# pw_dist_v2.net
KiCad netlist of a schematic drawn in EAGLE
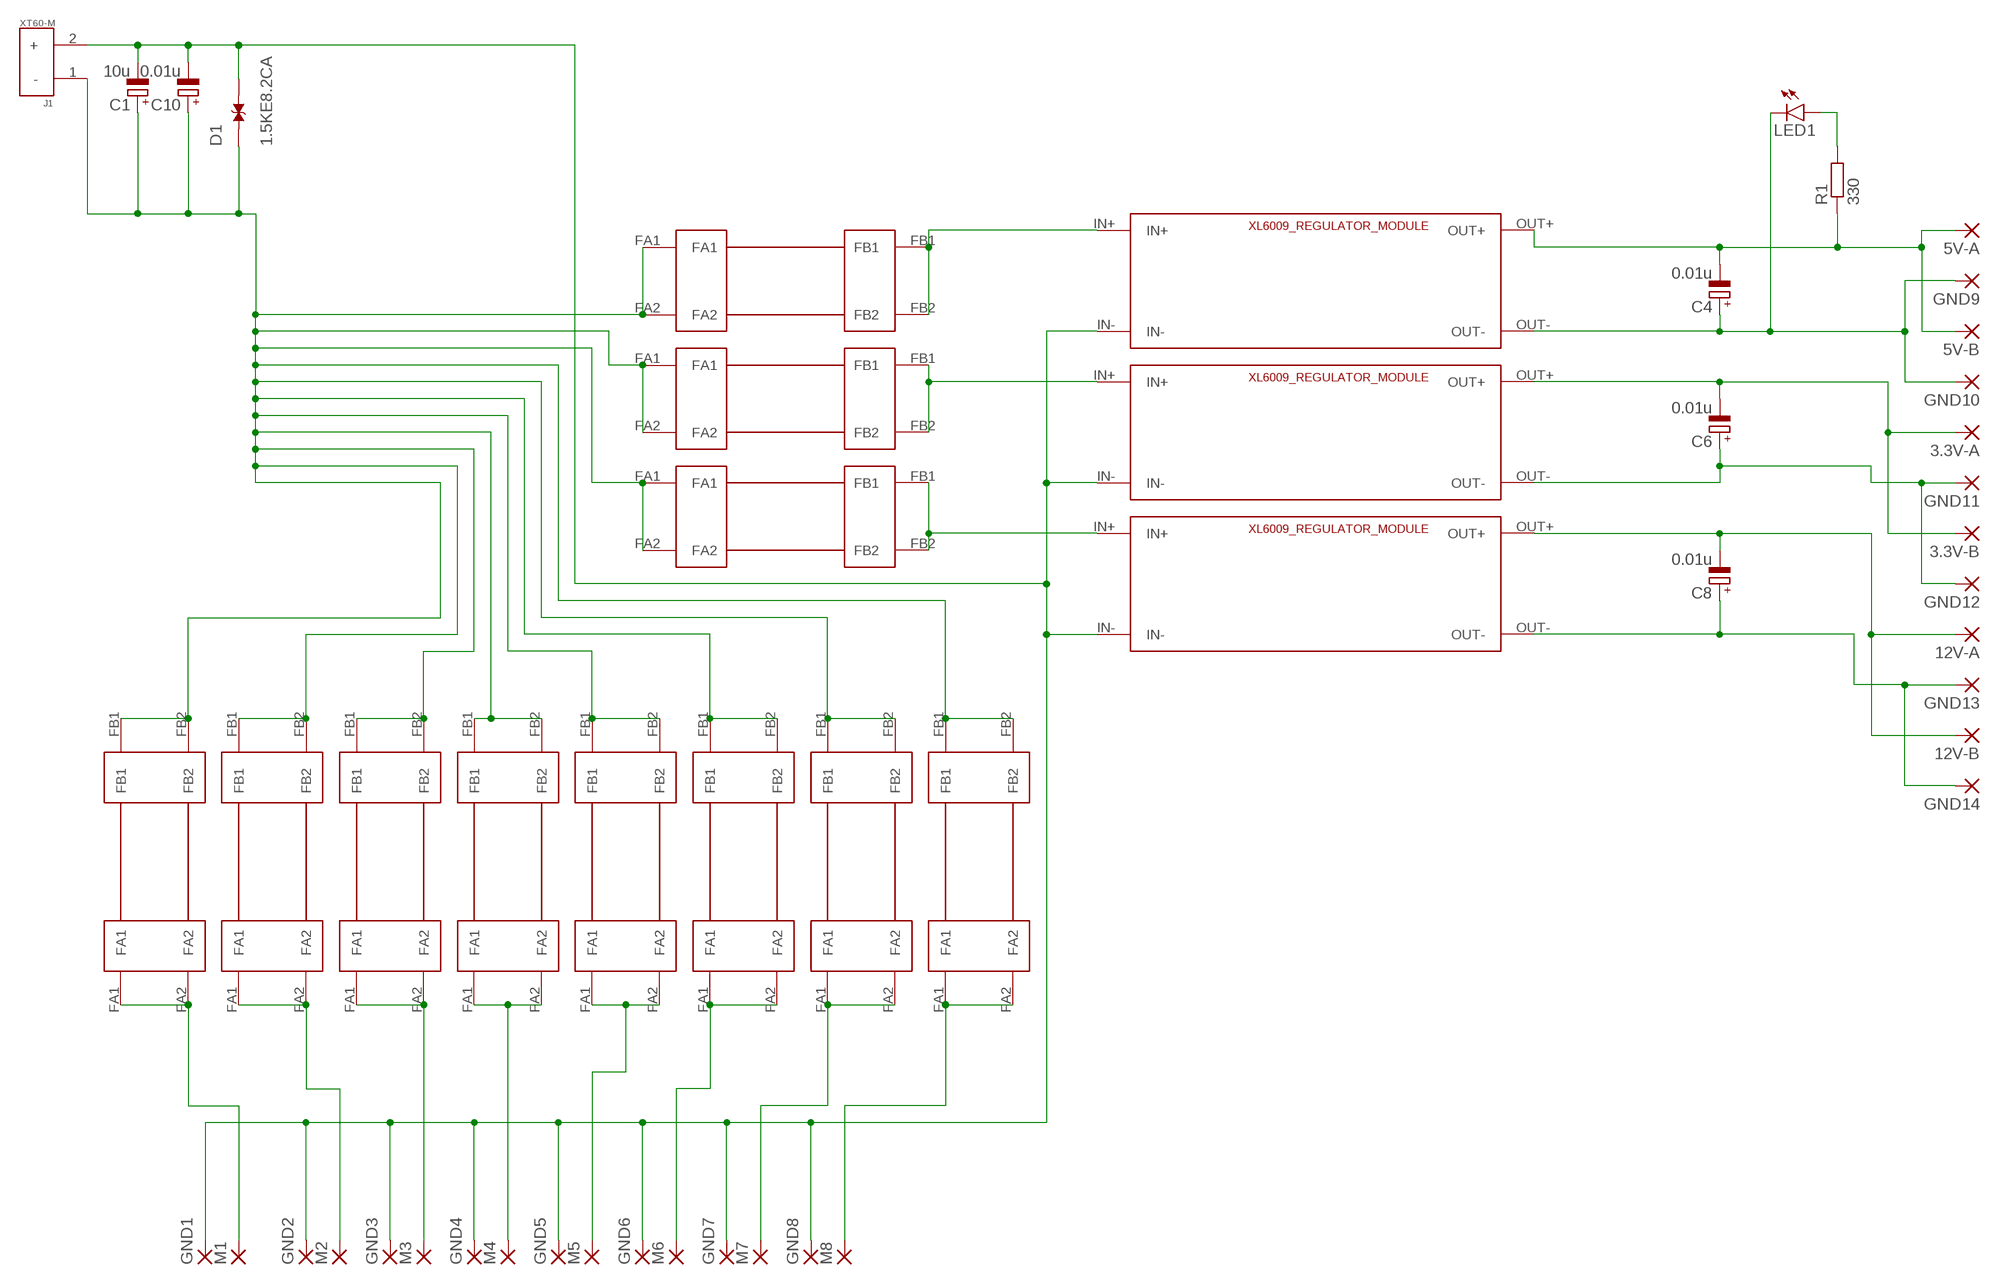
[diagram p0: schematic, sheet 1]

(export (version "E")
  (design (tool "Eeschema 10.0.6"))
  (components
    (comp (ref "3.3V-A")
      (value "SMD5")
      (footprint "eagle-import:SMD2,54-5,08")
      (libsource (lib "eagle-import") (part "SMD5"))
    )
    (comp (ref "3.3V-B")
      (value "SMD5")
      (footprint "eagle-import:SMD2,54-5,08")
      (libsource (lib "eagle-import") (part "SMD5"))
    )
    (comp (ref "5V-A")
      (value "SMD5")
      (footprint "eagle-import:SMD2,54-5,08")
      (libsource (lib "eagle-import") (part "SMD5"))
    )
    (comp (ref "5V-B")
      (value "SMD5")
      (footprint "eagle-import:SMD2,54-5,08")
      (libsource (lib "eagle-import") (part "SMD5"))
    )
    (comp (ref "12V-A")
      (value "SMD5")
      (footprint "eagle-import:SMD2,54-5,08")
      (libsource (lib "eagle-import") (part "SMD5"))
    )
    (comp (ref "12V-B")
      (value "SMD5")
      (footprint "eagle-import:SMD2,54-5,08")
      (libsource (lib "eagle-import") (part "SMD5"))
    )
    (comp (ref "C1")
      (value "10u")
      (footprint "eagle-import:E5-10,5")
      (libsource (lib "eagle-import") (part "CPOL-EUE5-10.5"))
    )
    (comp (ref "C4")
      (value "0.01u")
      (footprint "eagle-import:E5-10,5")
      (libsource (lib "eagle-import") (part "CPOL-EUE5-10.5"))
    )
    (comp (ref "C6")
      (value "0.01u")
      (footprint "eagle-import:E5-10,5")
      (libsource (lib "eagle-import") (part "CPOL-EUE5-10.5"))
    )
    (comp (ref "C8")
      (value "0.01u")
      (footprint "eagle-import:E5-10,5")
      (libsource (lib "eagle-import") (part "CPOL-EUE5-10.5"))
    )
    (comp (ref "C10")
      (value "0.01u")
      (footprint "eagle-import:E5-10,5")
      (libsource (lib "eagle-import") (part "CPOL-EUE5-10.5"))
    )
    (comp (ref "D1")
      (value "1.5KE8.2CA")
      (footprint "eagle-import:DIOAD1586W101L900D530")
      (fields (field (name "MF") "Taiwan Semiconductor"))
      (libsource (lib "eagle-import") (part "1.5KE8.2CA"))
    )
    (comp (ref "GND1")
      (value "SMD5")
      (footprint "eagle-import:SMD2,54-5,08")
      (libsource (lib "eagle-import") (part "SMD5"))
    )
    (comp (ref "GND2")
      (value "SMD5")
      (footprint "eagle-import:SMD2,54-5,08")
      (libsource (lib "eagle-import") (part "SMD5"))
    )
    (comp (ref "GND3")
      (value "SMD5")
      (footprint "eagle-import:SMD2,54-5,08")
      (libsource (lib "eagle-import") (part "SMD5"))
    )
    (comp (ref "GND4")
      (value "SMD5")
      (footprint "eagle-import:SMD2,54-5,08")
      (libsource (lib "eagle-import") (part "SMD5"))
    )
    (comp (ref "GND5")
      (value "SMD5")
      (footprint "eagle-import:SMD2,54-5,08")
      (libsource (lib "eagle-import") (part "SMD5"))
    )
    (comp (ref "GND6")
      (value "SMD5")
      (footprint "eagle-import:SMD2,54-5,08")
      (libsource (lib "eagle-import") (part "SMD5"))
    )
    (comp (ref "GND7")
      (value "SMD5")
      (footprint "eagle-import:SMD2,54-5,08")
      (libsource (lib "eagle-import") (part "SMD5"))
    )
    (comp (ref "GND8")
      (value "SMD5")
      (footprint "eagle-import:SMD2,54-5,08")
      (libsource (lib "eagle-import") (part "SMD5"))
    )
    (comp (ref "GND9")
      (value "SMD5")
      (footprint "eagle-import:SMD2,54-5,08")
      (libsource (lib "eagle-import") (part "SMD5"))
    )
    (comp (ref "GND10")
      (value "SMD5")
      (footprint "eagle-import:SMD2,54-5,08")
      (libsource (lib "eagle-import") (part "SMD5"))
    )
    (comp (ref "GND11")
      (value "SMD5")
      (footprint "eagle-import:SMD2,54-5,08")
      (libsource (lib "eagle-import") (part "SMD5"))
    )
    (comp (ref "GND12")
      (value "SMD5")
      (footprint "eagle-import:SMD2,54-5,08")
      (libsource (lib "eagle-import") (part "SMD5"))
    )
    (comp (ref "GND13")
      (value "SMD5")
      (footprint "eagle-import:SMD2,54-5,08")
      (libsource (lib "eagle-import") (part "SMD5"))
    )
    (comp (ref "GND14")
      (value "SMD5")
      (footprint "eagle-import:SMD2,54-5,08")
      (libsource (lib "eagle-import") (part "SMD5"))
    )
    (comp (ref "J1")
      (value "XT60-M")
      (footprint "eagle-import:AMASS_XT60-M")
      (fields (field (name "MF") "AMASS"))
      (libsource (lib "eagle-import") (part "XT60-M"))
    )
    (comp (ref "LED1")
      (value "LED5MM")
      (footprint "eagle-import:LED5MM")
      (libsource (lib "eagle-import") (part "LED5MM"))
    )
    (comp (ref "M1")
      (value "SMD5")
      (footprint "eagle-import:SMD2,54-5,08")
      (libsource (lib "eagle-import") (part "SMD5"))
    )
    (comp (ref "M2")
      (value "SMD5")
      (footprint "eagle-import:SMD2,54-5,08")
      (libsource (lib "eagle-import") (part "SMD5"))
    )
    (comp (ref "M3")
      (value "SMD5")
      (footprint "eagle-import:SMD2,54-5,08")
      (libsource (lib "eagle-import") (part "SMD5"))
    )
    (comp (ref "M4")
      (value "SMD5")
      (footprint "eagle-import:SMD2,54-5,08")
      (libsource (lib "eagle-import") (part "SMD5"))
    )
    (comp (ref "M5")
      (value "SMD5")
      (footprint "eagle-import:SMD2,54-5,08")
      (libsource (lib "eagle-import") (part "SMD5"))
    )
    (comp (ref "M6")
      (value "SMD5")
      (footprint "eagle-import:SMD2,54-5,08")
      (libsource (lib "eagle-import") (part "SMD5"))
    )
    (comp (ref "M7")
      (value "SMD5")
      (footprint "eagle-import:SMD2,54-5,08")
      (libsource (lib "eagle-import") (part "SMD5"))
    )
    (comp (ref "M8")
      (value "SMD5")
      (footprint "eagle-import:SMD2,54-5,08")
      (libsource (lib "eagle-import") (part "SMD5"))
    )
    (comp (ref "R1")
      (value "330")
      (footprint "eagle-import:0207_10")
      (libsource (lib "eagle-import") (part "R-EU_0207/10"))
    )
    (comp (ref "U$1")
      (value "XL6009_MODULE")
      (footprint "eagle-import:XL6009_MODULE")
      (libsource (lib "eagle-import") (part "power_dist_36414973_XL6009_MODULE"))
    )
    (comp (ref "U$2")
      (value "XL6009_MODULE")
      (footprint "eagle-import:XL6009_MODULE")
      (libsource (lib "eagle-import") (part "power_dist_36414973_XL6009_MODULE"))
    )
    (comp (ref "U$3")
      (value "XL6009_MODULE")
      (footprint "eagle-import:XL6009_MODULE")
      (libsource (lib "eagle-import") (part "XL6009_MODULE"))
    )
    (comp (ref "U$4")
      (value "FUSE_HOLDER_2")
      (footprint "eagle-import:FUSE_HOLDER_2")
      (libsource (lib "eagle-import") (part "FUSE_HOLDER_2"))
    )
    (comp (ref "U$5")
      (value "FUSE_HOLDER_2")
      (footprint "eagle-import:FUSE_HOLDER_2")
      (libsource (lib "eagle-import") (part "FUSE_HOLDER_2"))
    )
    (comp (ref "U$6")
      (value "FUSE_HOLDER_2")
      (footprint "eagle-import:FUSE_HOLDER_2")
      (libsource (lib "eagle-import") (part "FUSE_HOLDER_2"))
    )
    (comp (ref "U$7")
      (value "FUSE_HOLDER_2")
      (footprint "eagle-import:FUSE_HOLDER_2")
      (libsource (lib "eagle-import") (part "FUSE_HOLDER_2"))
    )
    (comp (ref "U$8")
      (value "FUSE_HOLDER_2")
      (footprint "eagle-import:FUSE_HOLDER_2")
      (libsource (lib "eagle-import") (part "FUSE_HOLDER_2"))
    )
    (comp (ref "U$9")
      (value "FUSE_HOLDER_2")
      (footprint "eagle-import:FUSE_HOLDER_2")
      (libsource (lib "eagle-import") (part "FUSE_HOLDER_2"))
    )
    (comp (ref "U$10")
      (value "FUSE_HOLDER_2")
      (footprint "eagle-import:FUSE_HOLDER_2")
      (libsource (lib "eagle-import") (part "FUSE_HOLDER_2"))
    )
    (comp (ref "U$11")
      (value "FUSE_HOLDER_2")
      (footprint "eagle-import:FUSE_HOLDER_2")
      (libsource (lib "eagle-import") (part "FUSE_HOLDER_2"))
    )
    (comp (ref "U$12")
      (value "FUSE_HOLDER_2")
      (footprint "eagle-import:FUSE_HOLDER_2")
      (libsource (lib "eagle-import") (part "FUSE_HOLDER_2"))
    )
    (comp (ref "U$13")
      (value "FUSE_HOLDER_2")
      (footprint "eagle-import:FUSE_HOLDER_2")
      (libsource (lib "eagle-import") (part "FUSE_HOLDER_2"))
    )
    (comp (ref "U$14")
      (value "FUSE_HOLDER_2")
      (footprint "eagle-import:FUSE_HOLDER_2")
      (libsource (lib "eagle-import") (part "FUSE_HOLDER_2"))
    )
  )
  (nets
    (net (code "1") (name "Net-(3.3V-A-P)") (class "Default")
      (node (ref "3.3V-A") (pin "1") (pinfunction "P_1") (pintype "passive"))
      (node (ref "3.3V-B") (pin "1") (pinfunction "P_1") (pintype "passive"))
      (node (ref "C6") (pin "-") (pinfunction "-_-") (pintype "passive"))
      (node (ref "U$1") (pin "OUT+") (pinfunction "OUT+_OUT+") (pintype "bidirectional"))
    )
    (net (code "2") (name "Net-(5V-A-P)") (class "Default")
      (node (ref "5V-A") (pin "1") (pinfunction "P_1") (pintype "passive"))
      (node (ref "5V-B") (pin "1") (pinfunction "P_1") (pintype "passive"))
      (node (ref "C4") (pin "-") (pinfunction "-_-") (pintype "passive"))
      (node (ref "R1") (pin "1") (pinfunction "1_1") (pintype "passive"))
      (node (ref "U$2") (pin "OUT+") (pinfunction "OUT+_OUT+") (pintype "bidirectional"))
    )
    (net (code "3") (name "Net-(12V-A-P)") (class "Default")
      (node (ref "12V-A") (pin "1") (pinfunction "P_1") (pintype "passive"))
      (node (ref "12V-B") (pin "1") (pinfunction "P_1") (pintype "passive"))
      (node (ref "C8") (pin "-") (pinfunction "-_-") (pintype "passive"))
      (node (ref "U$3") (pin "OUT+") (pinfunction "OUT+_OUT+") (pintype "bidirectional"))
    )
    (net (code "4") (name "Net-(GND1-P)") (class "Default")
      (node (ref "C1") (pin "-") (pinfunction "-_-") (pintype "passive"))
      (node (ref "C10") (pin "-") (pinfunction "-_-") (pintype "passive"))
      (node (ref "D1") (pin "2") (pinfunction "2_2") (pintype "passive"))
      (node (ref "GND1") (pin "1") (pinfunction "P_1") (pintype "passive"))
      (node (ref "GND2") (pin "1") (pinfunction "P_1") (pintype "passive"))
      (node (ref "GND3") (pin "1") (pinfunction "P_1") (pintype "passive"))
      (node (ref "GND4") (pin "1") (pinfunction "P_1") (pintype "passive"))
      (node (ref "GND5") (pin "1") (pinfunction "P_1") (pintype "passive"))
      (node (ref "GND6") (pin "1") (pinfunction "P_1") (pintype "passive"))
      (node (ref "GND7") (pin "1") (pinfunction "P_1") (pintype "passive"))
      (node (ref "GND8") (pin "1") (pinfunction "P_1") (pintype "passive"))
      (node (ref "J1") (pin "2") (pinfunction "+_2") (pintype "passive"))
      (node (ref "U$1") (pin "IN-") (pinfunction "IN-_IN-") (pintype "bidirectional"))
      (node (ref "U$2") (pin "IN-") (pinfunction "IN-_IN-") (pintype "bidirectional"))
      (node (ref "U$3") (pin "IN-") (pinfunction "IN-_IN-") (pintype "bidirectional"))
    )
    (net (code "5") (name "Net-(GND10-P)") (class "Default")
      (node (ref "C4") (pin "+") (pinfunction "+_+") (pintype "passive"))
      (node (ref "GND10") (pin "1") (pinfunction "P_1") (pintype "passive"))
      (node (ref "GND9") (pin "1") (pinfunction "P_1") (pintype "passive"))
      (node (ref "LED1") (pin "K") (pinfunction "C_K") (pintype "passive"))
      (node (ref "U$2") (pin "OUT-") (pinfunction "OUT-_OUT-") (pintype "bidirectional"))
    )
    (net (code "6") (name "Net-(GND11-P)") (class "Default")
      (node (ref "C6") (pin "+") (pinfunction "+_+") (pintype "passive"))
      (node (ref "GND11") (pin "1") (pinfunction "P_1") (pintype "passive"))
      (node (ref "GND12") (pin "1") (pinfunction "P_1") (pintype "passive"))
      (node (ref "U$1") (pin "OUT-") (pinfunction "OUT-_OUT-") (pintype "bidirectional"))
    )
    (net (code "7") (name "Net-(GND13-P)") (class "Default")
      (node (ref "C8") (pin "+") (pinfunction "+_+") (pintype "passive"))
      (node (ref "GND13") (pin "1") (pinfunction "P_1") (pintype "passive"))
      (node (ref "GND14") (pin "1") (pinfunction "P_1") (pintype "passive"))
      (node (ref "U$3") (pin "OUT-") (pinfunction "OUT-_OUT-") (pintype "bidirectional"))
    )
    (net (code "8") (name "Net-(J1--)") (class "Default")
      (node (ref "C1") (pin "+") (pinfunction "+_+") (pintype "passive"))
      (node (ref "C10") (pin "+") (pinfunction "+_+") (pintype "passive"))
      (node (ref "D1") (pin "1") (pinfunction "1_1") (pintype "passive"))
      (node (ref "J1") (pin "1") (pinfunction "-_1") (pintype "passive"))
      (node (ref "U$10") (pin "FB1") (pinfunction "FB1_FB1") (pintype "bidirectional"))
      (node (ref "U$10") (pin "FB2") (pinfunction "FB2_FB2") (pintype "bidirectional"))
      (node (ref "U$11") (pin "FB1") (pinfunction "FB1_FB1") (pintype "bidirectional"))
      (node (ref "U$11") (pin "FB2") (pinfunction "FB2_FB2") (pintype "bidirectional"))
      (node (ref "U$12") (pin "FB1") (pinfunction "FB1_FB1") (pintype "bidirectional"))
      (node (ref "U$12") (pin "FB2") (pinfunction "FB2_FB2") (pintype "bidirectional"))
      (node (ref "U$13") (pin "FB1") (pinfunction "FB1_FB1") (pintype "bidirectional"))
      (node (ref "U$13") (pin "FB2") (pinfunction "FB2_FB2") (pintype "bidirectional"))
      (node (ref "U$14") (pin "FB1") (pinfunction "FB1_FB1") (pintype "bidirectional"))
      (node (ref "U$14") (pin "FB2") (pinfunction "FB2_FB2") (pintype "bidirectional"))
      (node (ref "U$4") (pin "FA1") (pinfunction "FA1_FA1") (pintype "bidirectional"))
      (node (ref "U$4") (pin "FA2") (pinfunction "FA2_FA2") (pintype "bidirectional"))
      (node (ref "U$5") (pin "FA1") (pinfunction "FA1_FA1") (pintype "bidirectional"))
      (node (ref "U$5") (pin "FA2") (pinfunction "FA2_FA2") (pintype "bidirectional"))
      (node (ref "U$6") (pin "FA1") (pinfunction "FA1_FA1") (pintype "bidirectional"))
      (node (ref "U$6") (pin "FA2") (pinfunction "FA2_FA2") (pintype "bidirectional"))
      (node (ref "U$7") (pin "FB1") (pinfunction "FB1_FB1") (pintype "bidirectional"))
      (node (ref "U$7") (pin "FB2") (pinfunction "FB2_FB2") (pintype "bidirectional"))
      (node (ref "U$8") (pin "FB1") (pinfunction "FB1_FB1") (pintype "bidirectional"))
      (node (ref "U$8") (pin "FB2") (pinfunction "FB2_FB2") (pintype "bidirectional"))
      (node (ref "U$9") (pin "FB1") (pinfunction "FB1_FB1") (pintype "bidirectional"))
      (node (ref "U$9") (pin "FB2") (pinfunction "FB2_FB2") (pintype "bidirectional"))
    )
    (net (code "9") (name "Net-(LED1-PadA)") (class "Default")
      (node (ref "LED1") (pin "A") (pinfunction "A_A") (pintype "passive"))
      (node (ref "R1") (pin "2") (pinfunction "2_2") (pintype "passive"))
    )
    (net (code "10") (name "Net-(M1-P)") (class "Default")
      (node (ref "M1") (pin "1") (pinfunction "P_1") (pintype "passive"))
      (node (ref "U$14") (pin "FA1") (pinfunction "FA1_FA1") (pintype "bidirectional"))
      (node (ref "U$14") (pin "FA2") (pinfunction "FA2_FA2") (pintype "bidirectional"))
    )
    (net (code "11") (name "Net-(M2-P)") (class "Default")
      (node (ref "M2") (pin "1") (pinfunction "P_1") (pintype "passive"))
      (node (ref "U$13") (pin "FA1") (pinfunction "FA1_FA1") (pintype "bidirectional"))
      (node (ref "U$13") (pin "FA2") (pinfunction "FA2_FA2") (pintype "bidirectional"))
    )
    (net (code "12") (name "Net-(M3-P)") (class "Default")
      (node (ref "M3") (pin "1") (pinfunction "P_1") (pintype "passive"))
      (node (ref "U$12") (pin "FA1") (pinfunction "FA1_FA1") (pintype "bidirectional"))
      (node (ref "U$12") (pin "FA2") (pinfunction "FA2_FA2") (pintype "bidirectional"))
    )
    (net (code "13") (name "Net-(M4-P)") (class "Default")
      (node (ref "M4") (pin "1") (pinfunction "P_1") (pintype "passive"))
      (node (ref "U$11") (pin "FA1") (pinfunction "FA1_FA1") (pintype "bidirectional"))
      (node (ref "U$11") (pin "FA2") (pinfunction "FA2_FA2") (pintype "bidirectional"))
    )
    (net (code "14") (name "Net-(M5-P)") (class "Default")
      (node (ref "M5") (pin "1") (pinfunction "P_1") (pintype "passive"))
      (node (ref "U$10") (pin "FA1") (pinfunction "FA1_FA1") (pintype "bidirectional"))
      (node (ref "U$10") (pin "FA2") (pinfunction "FA2_FA2") (pintype "bidirectional"))
    )
    (net (code "15") (name "Net-(M6-P)") (class "Default")
      (node (ref "M6") (pin "1") (pinfunction "P_1") (pintype "passive"))
      (node (ref "U$9") (pin "FA1") (pinfunction "FA1_FA1") (pintype "bidirectional"))
      (node (ref "U$9") (pin "FA2") (pinfunction "FA2_FA2") (pintype "bidirectional"))
    )
    (net (code "16") (name "Net-(M7-P)") (class "Default")
      (node (ref "M7") (pin "1") (pinfunction "P_1") (pintype "passive"))
      (node (ref "U$8") (pin "FA1") (pinfunction "FA1_FA1") (pintype "bidirectional"))
      (node (ref "U$8") (pin "FA2") (pinfunction "FA2_FA2") (pintype "bidirectional"))
    )
    (net (code "17") (name "Net-(M8-P)") (class "Default")
      (node (ref "M8") (pin "1") (pinfunction "P_1") (pintype "passive"))
      (node (ref "U$7") (pin "FA1") (pinfunction "FA1_FA1") (pintype "bidirectional"))
      (node (ref "U$7") (pin "FA2") (pinfunction "FA2_FA2") (pintype "bidirectional"))
    )
    (net (code "18") (name "Net-(U$1-PadIN+)") (class "Default")
      (node (ref "U$1") (pin "IN+") (pinfunction "IN+_IN+") (pintype "bidirectional"))
      (node (ref "U$5") (pin "FB1") (pinfunction "FB1_FB1") (pintype "bidirectional"))
      (node (ref "U$5") (pin "FB2") (pinfunction "FB2_FB2") (pintype "bidirectional"))
    )
    (net (code "19") (name "Net-(U$2-PadIN+)") (class "Default")
      (node (ref "U$2") (pin "IN+") (pinfunction "IN+_IN+") (pintype "bidirectional"))
      (node (ref "U$4") (pin "FB1") (pinfunction "FB1_FB1") (pintype "bidirectional"))
      (node (ref "U$4") (pin "FB2") (pinfunction "FB2_FB2") (pintype "bidirectional"))
    )
    (net (code "20") (name "Net-(U$3-PadIN+)") (class "Default")
      (node (ref "U$3") (pin "IN+") (pinfunction "IN+_IN+") (pintype "bidirectional"))
      (node (ref "U$6") (pin "FB1") (pinfunction "FB1_FB1") (pintype "bidirectional"))
      (node (ref "U$6") (pin "FB2") (pinfunction "FB2_FB2") (pintype "bidirectional"))
    )
  )
)
